# PROC106B_ANALOG_MUX.net
KiCad netlist of a schematic drawn in Altium Designer
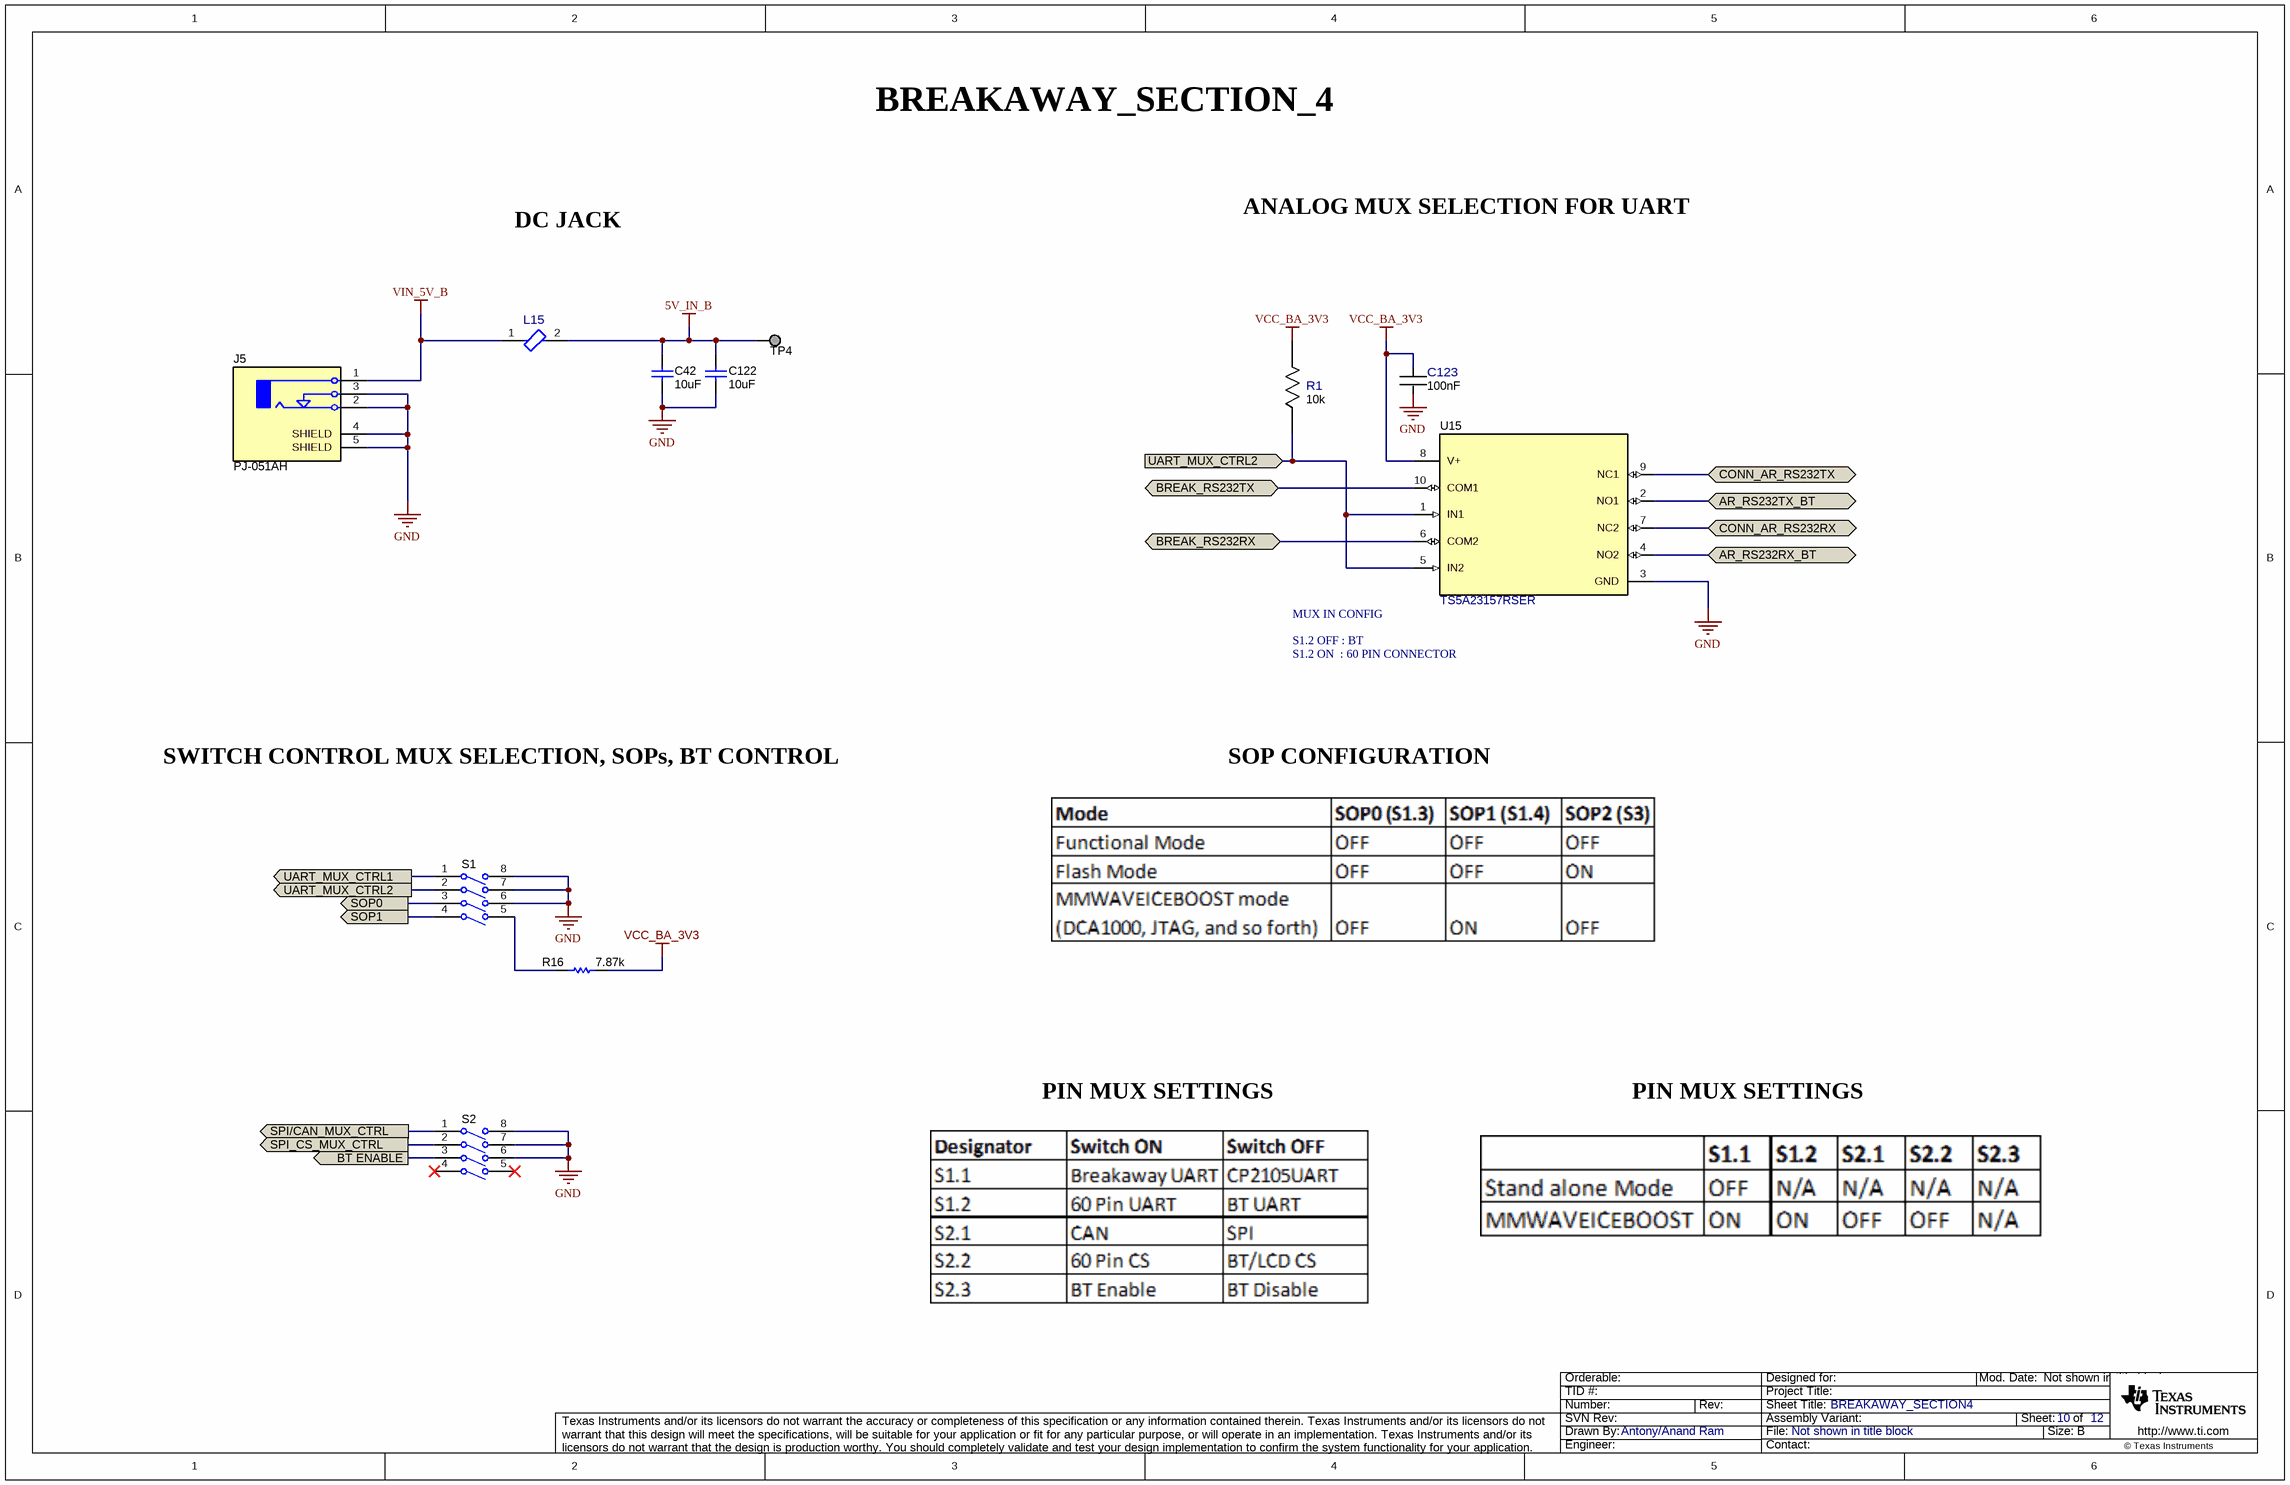
[diagram p0: PROC106B_ANALOG_MUX.SchDoc]

(export (version "E")
  (design (tool "Eeschema 10.0.6"))
  (components
    (comp (ref "C42")
      (value "10uF")
      (footprint "0402_070")
      (description "CAP, CERM, 10 uF, 10 V, +/- 20%, X5R, 0402")
      (fields
        (field (name "MANUFACTURER") "Samsung Electro-Mechanics")
        (field (name "PARTNUMBER") "CL05A106MP5NUNC")
      )
      (libsource (lib "Altium Vault - TI") (part "Capacitor"))
    )
    (comp (ref "C122")
      (value "10uF")
      (footprint "0402_070")
      (description "CAP, CERM, 10 uF, 10 V, +/- 20%, X5R, 0402")
      (fields
        (field (name "MANUFACTURER") "Samsung Electro-Mechanics")
        (field (name "PARTNUMBER") "CL05A106MP5NUNC")
      )
      (libsource (lib "Altium Vault - TI") (part "Capacitor"))
    )
    (comp (ref "C123")
      (value "GRM033R6YA104KE14D")
      (footprint "FP-GRM033R6YA104KE14D_0201 (0603 Metric)-IPC_C")
      (description "Cap Ceramic 0.1uF 35V X5R 10% Pad SMD 0201 85C T/R")
      (fields (field (name "CAP_F") "100nF") (field (name "MANUFACTURER") "Murata Electronics North America"))
      (libsource (lib "Altium Vault - TI") (part "SYM-B32642B0223J"))
    )
    (comp (ref "J5")
      (value "PJ-051AH")
      (footprint "CUI_PJ-051AH")
      (description "DC Power Jack, R/A, TH")
      (fields (field (name "MANUFACTURER") "CUI Inc."))
      (libsource (lib "Altium Vault - TI") (part "Audio_T2SW3S1_2Shield"))
    )
    (comp (ref "L15")
      (value "MPZ2012S101ATD25")
      (footprint "FP-MPZ2012S101ATD25_0805-MFG")
      (description "100 Ohms @ 100MHz 1 Power Line Ferrite Bead 0805 (2012 Metric) 4A 20mOhm")
      (fields (field (name "MANUFACTURER") "TDK") (field (name "DIGIKEY PART NUMBER") "445-172903-1-ND"))
      (libsource (lib "Altium Vault - TI") (part "SYM-MPZ2012S101ATD25"))
    )
    (comp (ref "R1")
      (value "RR0306P-103-D")
      (footprint "FP-RR0306P-103-D_0201-IPC_C")
      (description "10 kOhms ±0.5% 0.05W, 1/20W Chip Resistor 0201 (0603 Metric)  Thin Film")
      (fields (field (name "MANUFACTURER") "Susumu") (field (name "RES_OHM") "10k"))
      (libsource (lib "Altium Vault - TI") (part "SYM-PMR18EZPJ000"))
    )
    (comp (ref "R16")
      (value "7.87k")
      (footprint "0201L")
      (description "RES, 7.87 k, 1%, 0.05 W, 0201")
      (fields
        (field (name "MANUFACTURER") "Yageo America")
        (field (name "PARTNUMBER") "RC0201FR-077K87L")
        (field (name "PUBLISHER") "Texas Instruments")
      )
      (libsource (lib "Altium Vault - TI") (part "Resistor"))
    )
    (comp (ref "S1")
      (value "218-4LPST")
      (footprint "SW_218-4LPST")
      (description "Switch, Slide, SPST 4 poles, SMT")
      (fields
        (field (name "MANUFACTURER") "CTS Electrocomponents")
        (field (name "PUBLISHER") "Texas Instruments")
      )
      (libsource (lib "Altium Vault - TI") (part "SW_4SPST"))
    )
    (comp (ref "S2")
      (value "218-4LPST")
      (footprint "SW_218-4LPST")
      (description "Switch, Slide, SPST 4 poles, SMT")
      (fields
        (field (name "MANUFACTURER") "CTS Electrocomponents")
        (field (name "PUBLISHER") "Texas Instruments")
      )
      (libsource (lib "Altium Vault - TI") (part "SW_4SPST"))
    )
    (comp (ref "TP4")
      (value "TESTPOINT")
      (footprint "TP_25MIL-SMT")
      (description "TEST POINT.  No entry in BOM.")
      (libsource (lib "Altium Vault - TI") (part "TESTPOINT"))
    )
    (comp (ref "U15")
      (value "TS5A23157RSER")
      (footprint "RSE0010A")
      (description "Dual 10-ohm SPDT Analog Switch, RSE0010A (UQFN-10)")
      (fields
        (field (name "MANUFACTURER") "Texas Instruments")
        (field (name "PUBLISHER") "Texas Instruments")
      )
      (libsource (lib "Altium Vault - TI") (part "TS5A23159"))
    )
  )
  (nets
    (net (code "1") (name "/AR_RS232RX_BT") (class "Default")
      (node (ref "U15") (pin "4") (pinfunction "NO2_4") (pintype "bidirectional"))
    )
    (net (code "2") (name "/AR_RS232TX_BT") (class "Default")
      (node (ref "U15") (pin "2") (pinfunction "NO1_2") (pintype "bidirectional"))
    )
    (net (code "3") (name "/BREAK_RS232RX") (class "Default")
      (node (ref "U15") (pin "6") (pinfunction "COM2_6") (pintype "bidirectional"))
    )
    (net (code "4") (name "/BREAK_RS232TX") (class "Default")
      (node (ref "U15") (pin "10") (pinfunction "COM1_10") (pintype "bidirectional"))
    )
    (net (code "5") (name "/BT ENABLE") (class "Default")
      (node (ref "S2") (pin "3") (pinfunction "A3_3") (pintype "passive"))
    )
    (net (code "6") (name "/CONN_AR_RS232RX") (class "Default")
      (node (ref "U15") (pin "7") (pinfunction "NC2_7") (pintype "bidirectional"))
    )
    (net (code "7") (name "/CONN_AR_RS232TX") (class "Default")
      (node (ref "U15") (pin "9") (pinfunction "NC1_9") (pintype "bidirectional"))
    )
    (net (code "8") (name "/SOP0") (class "Default")
      (node (ref "S1") (pin "3") (pinfunction "A3_3") (pintype "passive"))
    )
    (net (code "9") (name "/SOP1") (class "Default")
      (node (ref "S1") (pin "4") (pinfunction "A4_4") (pintype "passive"))
    )
    (net (code "10") (name "/SPI_CS_MUX_CTRL") (class "Default")
      (node (ref "S2") (pin "2") (pinfunction "A2_2") (pintype "passive"))
    )
    (net (code "11") (name "/SPI{slash}CAN_MUX_CTRL") (class "Default")
      (node (ref "S2") (pin "1") (pinfunction "A1_1") (pintype "passive"))
    )
    (net (code "12") (name "/UART_MUX_CTRL1") (class "Default")
      (node (ref "S1") (pin "1") (pinfunction "A1_1") (pintype "passive"))
    )
    (net (code "13") (name "/UART_MUX_CTRL2") (class "Default")
      (node (ref "R1") (pin "1") (pinfunction "1_1") (pintype "passive"))
      (node (ref "S1") (pin "2") (pinfunction "A2_2") (pintype "passive"))
      (node (ref "U15") (pin "1") (pinfunction "IN1_1") (pintype "input"))
      (node (ref "U15") (pin "5") (pinfunction "IN2_5") (pintype "input"))
    )
    (net (code "14") (name "5V_IN_B") (class "Default")
      (node (ref "C122") (pin "1") (pinfunction "1_1") (pintype "passive"))
      (node (ref "C42") (pin "2") (pinfunction "2_2") (pintype "passive"))
      (node (ref "L15") (pin "2") (pinfunction "2_2") (pintype "passive"))
      (node (ref "TP4") (pin "1") (pintype "passive"))
    )
    (net (code "15") (name "GND") (class "Default")
      (node (ref "C122") (pin "2") (pinfunction "2_2") (pintype "passive"))
      (node (ref "C123") (pin "2") (pinfunction "2_2") (pintype "passive"))
      (node (ref "C42") (pin "1") (pinfunction "1_1") (pintype "passive"))
      (node (ref "J5") (pin "2") (pinfunction "TIP_2") (pintype "passive"))
      (node (ref "J5") (pin "3") (pinfunction "TIP_SWITCH_3") (pintype "passive"))
      (node (ref "J5") (pin "4") (pinfunction "SHIELD_4") (pintype "passive"))
      (node (ref "J5") (pin "5") (pinfunction "SHIELD_5") (pintype "passive"))
      (node (ref "S1") (pin "6") (pinfunction "B3_6") (pintype "passive"))
      (node (ref "S1") (pin "7") (pinfunction "B2_7") (pintype "passive"))
      (node (ref "S1") (pin "8") (pinfunction "B1_8") (pintype "passive"))
      (node (ref "S2") (pin "6") (pinfunction "B3_6") (pintype "passive"))
      (node (ref "S2") (pin "7") (pinfunction "B2_7") (pintype "passive"))
      (node (ref "S2") (pin "8") (pinfunction "B1_8") (pintype "passive"))
      (node (ref "U15") (pin "3") (pinfunction "GND_3") (pintype "power_in"))
    )
    (net (code "16") (name "Net-(S1-B4)") (class "Default")
      (node (ref "R16") (pin "2") (pinfunction "2_2") (pintype "passive"))
      (node (ref "S1") (pin "5") (pinfunction "B4_5") (pintype "passive"))
    )
    (net (code "17") (name "VCC_BA_3V3") (class "Default")
      (node (ref "C123") (pin "1") (pinfunction "1_1") (pintype "passive"))
      (node (ref "R1") (pin "2") (pinfunction "2_2") (pintype "passive"))
      (node (ref "R16") (pin "1") (pinfunction "1_1") (pintype "passive"))
      (node (ref "U15") (pin "8") (pinfunction "V+_8") (pintype "power_in"))
    )
    (net (code "18") (name "VIN_5V_B") (class "Default")
      (node (ref "J5") (pin "1") (pinfunction "SLEEVE_1") (pintype "passive"))
      (node (ref "L15") (pin "1") (pinfunction "1_1") (pintype "passive"))
    )
    (net (code "19") (name "unconnected-(S2-A4-Pad4)") (class "Default")
      (node (ref "S2") (pin "4") (pinfunction "A4_4") (pintype "passive+no_connect"))
    )
    (net (code "20") (name "unconnected-(S2-B4-Pad5)") (class "Default")
      (node (ref "S2") (pin "5") (pinfunction "B4_5") (pintype "passive+no_connect"))
    )
  )
)
